# CLK_SYNC.net
KiCad netlist of a schematic drawn in Altium Designer
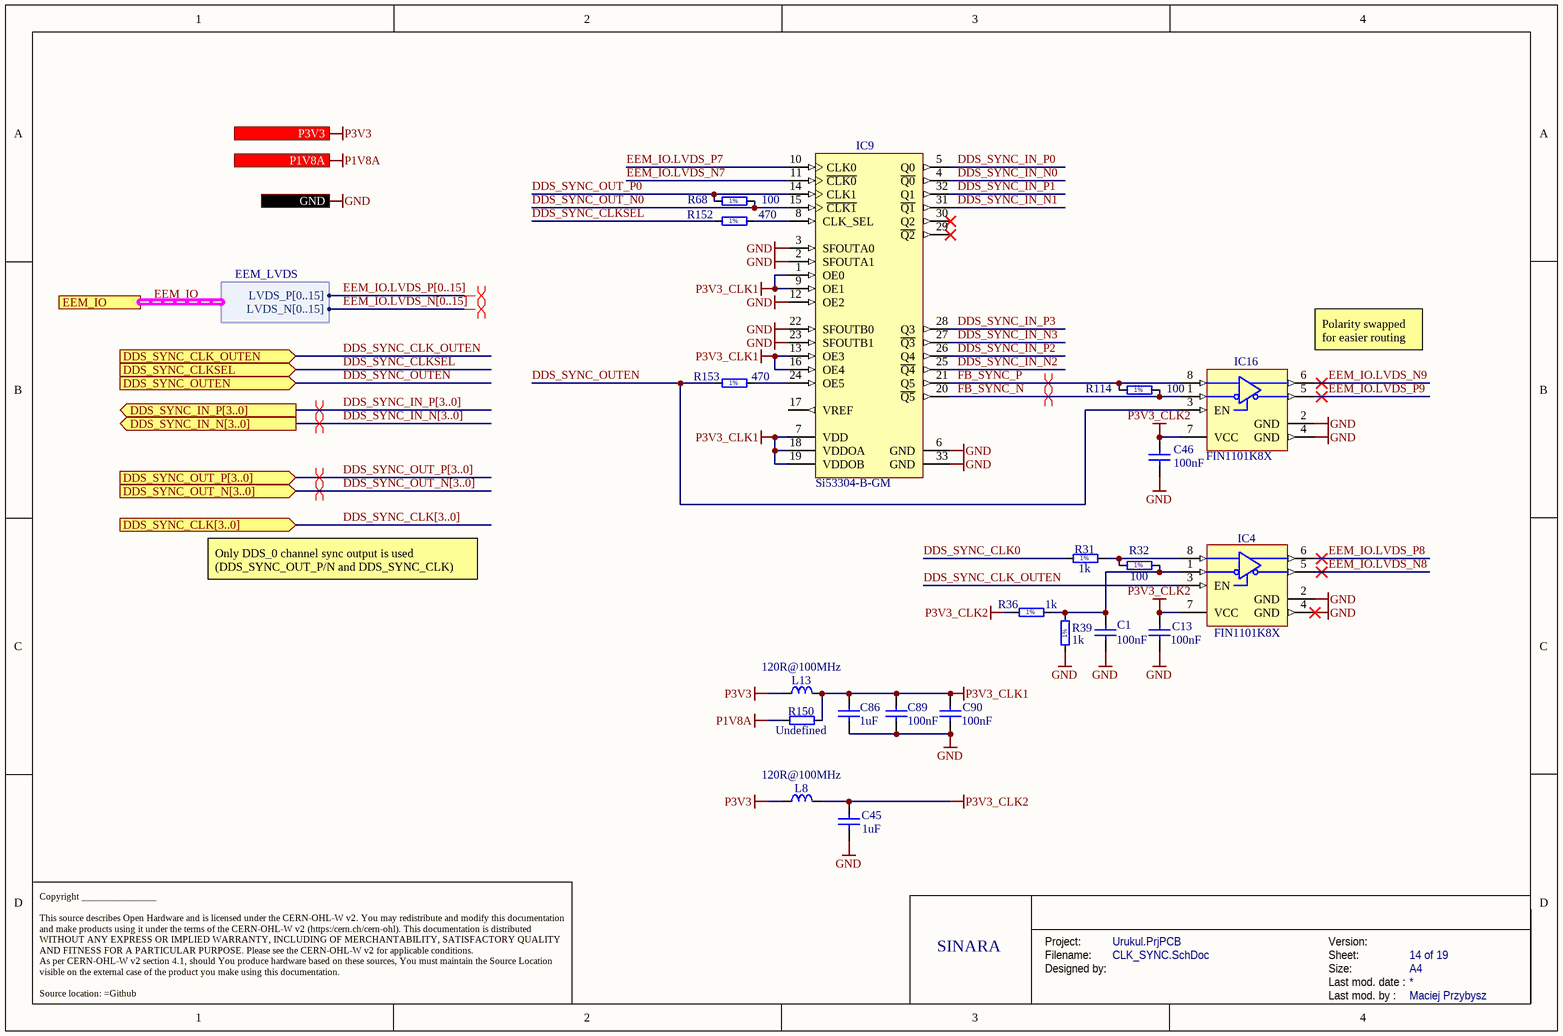
[diagram p0: CLK_SYNC.SchDoc]

(export (version "E")
  (design (tool "Eeschema 10.0.6"))
  (components
    (comp (ref "C1")
      (value "100nF")
      (footprint "CAPC1005X55N")
      (description "Non-polarised capacitor")
      (fields
        (field (name "PART NUMBER") "CC0402_100NF_16V_10%_X5R")
        (field (name "VOLTAGE") "16V")
        (field (name "AUTHOR") "CERN DEM JLC")
      )
      (libsource (lib "Capacitors") (part "Capacitor - non polarized"))
    )
    (comp (ref "C13")
      (value "100nF")
      (footprint "CAPC1005X55N")
      (description "Non-polarised capacitor")
      (fields
        (field (name "PART NUMBER") "CC0402_100NF_16V_10%_X5R")
        (field (name "VOLTAGE") "16V")
        (field (name "AUTHOR") "CERN DEM JLC")
      )
      (libsource (lib "Capacitors") (part "Capacitor - non polarized"))
    )
    (comp (ref "C45")
      (value "1uF")
      (footprint "CAPC1005X55N")
      (description "Non-polarised capacitor")
      (fields
        (field (name "PART NUMBER") "CC0402_1UF_16V_10%_X5R")
        (field (name "VOLTAGE") "16V")
        (field (name "AUTHOR") "CERN DEM JLC")
      )
      (libsource (lib "Capacitors") (part "Capacitor - non polarized"))
    )
    (comp (ref "C46")
      (value "100nF")
      (footprint "CAPC1005X55N")
      (description "Non-polarised capacitor")
      (fields
        (field (name "PART NUMBER") "CC0402_100NF_16V_10%_X5R")
        (field (name "VOLTAGE") "16V")
        (field (name "AUTHOR") "CERN DEM JLC")
      )
      (libsource (lib "Capacitors") (part "Capacitor - non polarized"))
    )
    (comp (ref "C86")
      (value "1uF")
      (footprint "CAPC1005X55N")
      (description "Non-polarised capacitor")
      (fields
        (field (name "PART NUMBER") "CC0402_1UF_16V_10%_X5R")
        (field (name "VOLTAGE") "16V")
        (field (name "AUTHOR") "CERN DEM JLC")
      )
      (libsource (lib "Capacitors") (part "Capacitor - non polarized"))
    )
    (comp (ref "C89")
      (value "100nF")
      (footprint "CAPC1005X55N")
      (description "Non-polarised capacitor")
      (fields
        (field (name "PART NUMBER") "CC0402_100NF_16V_10%_X5R")
        (field (name "VOLTAGE") "16V")
        (field (name "AUTHOR") "CERN DEM JLC")
      )
      (libsource (lib "Capacitors") (part "Capacitor - non polarized"))
    )
    (comp (ref "C90")
      (value "100nF")
      (footprint "CAPC1005X55N")
      (description "Non-polarised capacitor")
      (fields
        (field (name "PART NUMBER") "CC0402_100NF_16V_10%_X5R")
        (field (name "VOLTAGE") "16V")
        (field (name "AUTHOR") "CERN DEM JLC")
      )
      (libsource (lib "Capacitors") (part "Capacitor - non polarized"))
    )
    (comp (ref "IC4")
      (value "FIN1101K8X")
      (footprint "SOP50P310X90-8N")
      (description "LVDS Single Port High Speed Repeater")
      (fields (field (name "MANUFACTURER") "FAIRCHILD SEMICONDUCTOR") (field (name "AUTHOR") "CERN DEM JLC"))
      (libsource (lib "ICs And Semiconductors") (part "FIN1101K8X"))
    )
    (comp (ref "IC9")
      (value "Si53304-B-GM")
      (footprint "SLAB-QFN-32-2150x2150TP_M")
      (fields (field (name "MANUFACTURER") "Silicon Labs"))
      (libsource (lib "Altium Content Vault") (part "SLAB-Si533X4-QFN-32-33"))
    )
    (comp (ref "IC16")
      (value "FIN1101K8X")
      (footprint "SOP50P310X90-8N")
      (description "LVDS Single Port High Speed Repeater")
      (fields (field (name "MANUFACTURER") "FAIRCHILD SEMICONDUCTOR") (field (name "AUTHOR") "CERN DEM JLC"))
      (libsource (lib "ICs And Semiconductors") (part "FIN1101K8X"))
    )
    (comp (ref "L8")
      (value "120R@100MHz")
      (footprint "INDC1608X95N")
      (description "Inductor")
      (fields
        (field (name "PART NUMBER") "IND0603_MURATA_BLM18PG121SN1D")
        (field (name "POWER") "2A")
        (field (name "AUTHOR") "CERN DEM BC")
      )
      (libsource (lib "Inductors & Transformers") (part "Inductor"))
    )
    (comp (ref "L13")
      (value "120R@100MHz")
      (footprint "INDC1608X95N")
      (description "Inductor")
      (fields
        (field (name "PART NUMBER") "IND0603_MURATA_BLM18PG121SN1D")
        (field (name "POWER") "2A")
        (field (name "AUTHOR") "CERN DEM BC")
      )
      (libsource (lib "Inductors & Transformers") (part "Inductor"))
    )
    (comp (ref "R31")
      (value "1k")
      (footprint "RESC1005X40N")
      (description "Resistor - 1%")
      (fields
        (field (name "PART NUMBER") "R0402_1K_1%_0.0625W_100PPM")
        (field (name "POWER") "0.0625W")
        (field (name "AUTHOR") "CERN DEM JLC")
      )
      (libsource (lib "Resistors") (part "Resistor - 1%"))
    )
    (comp (ref "R32")
      (value "100")
      (footprint "RESC1005X40N")
      (description "Resistor - 1%")
      (fields
        (field (name "PART NUMBER") "R0402_100R_1%_0.0625W_100PPM")
        (field (name "POWER") "0.0625W")
        (field (name "AUTHOR") "CERN DEM JLC")
      )
      (libsource (lib "Resistors") (part "Resistor - 1%"))
    )
    (comp (ref "R36")
      (value "1k")
      (footprint "RESC1005X40N")
      (description "Resistor - 1%")
      (fields
        (field (name "PART NUMBER") "R0402_1K_1%_0.0625W_100PPM")
        (field (name "POWER") "0.0625W")
        (field (name "AUTHOR") "CERN DEM JLC")
      )
      (libsource (lib "Resistors") (part "Resistor - 1%"))
    )
    (comp (ref "R39")
      (value "1k")
      (footprint "RESC1005X40N")
      (description "Resistor - 1%")
      (fields
        (field (name "PART NUMBER") "R0402_1K_1%_0.0625W_100PPM")
        (field (name "POWER") "0.0625W")
        (field (name "AUTHOR") "CERN DEM JLC")
      )
      (libsource (lib "Resistors") (part "Resistor - 1%"))
    )
    (comp (ref "R68")
      (value "100")
      (footprint "RESC1005X40N")
      (description "Resistor - 1%")
      (fields
        (field (name "PART NUMBER") "R0402_100R_1%_0.0625W_100PPM")
        (field (name "POWER") "0.0625W")
        (field (name "AUTHOR") "CERN DEM JLC")
      )
      (libsource (lib "Resistors") (part "Resistor - 1%"))
    )
    (comp (ref "R114")
      (value "100")
      (footprint "RESC1005X40N")
      (description "Resistor - 1%")
      (fields
        (field (name "PART NUMBER") "R0402_100R_1%_0.0625W_100PPM")
        (field (name "POWER") "0.0625W")
        (field (name "AUTHOR") "CERN DEM JLC")
      )
      (libsource (lib "Resistors") (part "Resistor - 1%"))
    )
    (comp (ref "R150")
      (value "Undefined")
      (footprint "RESC1608X55N")
      (description "Resistor")
      (fields (field (name "PART NUMBER") "R0603_NO-VALUE") (field (name "AUTHOR") "CERN DEM JLC"))
      (libsource (lib "Resistors") (part "Resistor"))
    )
    (comp (ref "R152")
      (value "470")
      (footprint "RESC1005X40N")
      (description "Resistor - 1%")
      (fields
        (field (name "PART NUMBER") "R0402_470R_1%_0.0625W_100PPM")
        (field (name "POWER") "0.0625W")
        (field (name "AUTHOR") "CERN DEM JLC")
      )
      (libsource (lib "Resistors") (part "Resistor - 1%"))
    )
    (comp (ref "R153")
      (value "470")
      (footprint "RESC1005X40N")
      (description "Resistor - 1%")
      (fields
        (field (name "PART NUMBER") "R0402_470R_1%_0.0625W_100PPM")
        (field (name "POWER") "0.0625W")
        (field (name "AUTHOR") "CERN DEM JLC")
      )
      (libsource (lib "Resistors") (part "Resistor - 1%"))
    )
  )
  (nets
    (net (code "37") (name "/DDS_SYNC_CLK0") (class "Default")
      (node (ref "R31") (pin "1") (pinfunction "1_1") (pintype "passive"))
    )
    (net (code "38") (name "/DDS_SYNC_CLKSEL") (class "Default")
      (node (ref "R152") (pin "1") (pinfunction "1_1") (pintype "passive"))
    )
    (net (code "40") (name "/DDS_SYNC_CLK_OUTEN") (class "Default")
      (node (ref "IC4") (pin "3") (pinfunction "EN_3") (pintype "input"))
    )
    (net (code "41") (name "/DDS_SYNC_IN_N0") (class "Default")
      (node (ref "IC9") (pin "4") (pinfunction "~{Q0}_4") (pintype "output"))
    )
    (net (code "42") (name "/DDS_SYNC_IN_N1") (class "Default")
      (node (ref "IC9") (pin "31") (pinfunction "~{Q1}_31") (pintype "output"))
    )
    (net (code "43") (name "/DDS_SYNC_IN_N2") (class "Default")
      (node (ref "IC9") (pin "25") (pinfunction "~{Q4}_25") (pintype "output"))
    )
    (net (code "44") (name "/DDS_SYNC_IN_N3") (class "Default")
      (node (ref "IC9") (pin "27") (pinfunction "~{Q3}_27") (pintype "output"))
    )
    (net (code "46") (name "/DDS_SYNC_IN_P0") (class "Default")
      (node (ref "IC9") (pin "5") (pinfunction "Q0_5") (pintype "output"))
    )
    (net (code "47") (name "/DDS_SYNC_IN_P1") (class "Default")
      (node (ref "IC9") (pin "32") (pinfunction "Q1_32") (pintype "output"))
    )
    (net (code "48") (name "/DDS_SYNC_IN_P2") (class "Default")
      (node (ref "IC9") (pin "26") (pinfunction "Q4_26") (pintype "output"))
    )
    (net (code "49") (name "/DDS_SYNC_IN_P3") (class "Default")
      (node (ref "IC9") (pin "28") (pinfunction "Q3_28") (pintype "output"))
    )
    (net (code "51") (name "/DDS_SYNC_OUTEN") (class "Default")
      (node (ref "IC16") (pin "3") (pinfunction "EN_3") (pintype "input"))
      (node (ref "R153") (pin "1") (pinfunction "1_1") (pintype "passive"))
    )
    (net (code "52") (name "/DDS_SYNC_OUT_N0") (class "Default")
      (node (ref "IC9") (pin "15") (pinfunction "~{CLK1}_15") (pintype "input"))
      (node (ref "R68") (pin "2") (pinfunction "2_2") (pintype "passive"))
    )
    (net (code "54") (name "/DDS_SYNC_OUT_P0") (class "Default")
      (node (ref "IC9") (pin "14") (pinfunction "CLK1_14") (pintype "input"))
      (node (ref "R68") (pin "1") (pinfunction "1_1") (pintype "passive"))
    )
    (net (code "56") (name "/EEM_IO.LVDS_N7") (class "Default")
      (node (ref "IC9") (pin "11") (pinfunction "~{CLK0}_11") (pintype "input"))
    )
    (net (code "57") (name "/EEM_IO.LVDS_N8") (class "Default")
      (node (ref "IC4") (pin "5") (pinfunction "DOUT-_5") (pintype "output"))
    )
    (net (code "58") (name "/EEM_IO.LVDS_N9") (class "Default")
      (node (ref "IC16") (pin "6") (pinfunction "DOUT+_6") (pintype "output"))
    )
    (net (code "60") (name "/EEM_IO.LVDS_P7") (class "Default")
      (node (ref "IC9") (pin "10") (pinfunction "CLK0_10") (pintype "input"))
    )
    (net (code "61") (name "/EEM_IO.LVDS_P8") (class "Default")
      (node (ref "IC4") (pin "6") (pinfunction "DOUT+_6") (pintype "output"))
    )
    (net (code "62") (name "/EEM_IO.LVDS_P9") (class "Default")
      (node (ref "IC16") (pin "5") (pinfunction "DOUT-_5") (pintype "output"))
    )
    (net (code "65") (name "/FB_SYNC_N") (class "Default")
      (node (ref "IC16") (pin "1") (pinfunction "RIN-_1") (pintype "input"))
      (node (ref "IC9") (pin "20") (pinfunction "~{Q5}_20") (pintype "output"))
      (node (ref "R114") (pin "2") (pinfunction "2_2") (pintype "passive"))
    )
    (net (code "66") (name "/FB_SYNC_P") (class "Default")
      (node (ref "IC16") (pin "8") (pinfunction "RIN+_8") (pintype "input"))
      (node (ref "IC9") (pin "21") (pinfunction "Q5_21") (pintype "output"))
      (node (ref "R114") (pin "1") (pinfunction "1_1") (pintype "passive"))
    )
    (net (code "67") (name "GND") (class "Default")
      (node (ref "C1") (pin "1") (pinfunction "1_1") (pintype "passive"))
      (node (ref "C13") (pin "1") (pinfunction "1_1") (pintype "passive"))
      (node (ref "C45") (pin "1") (pinfunction "1_1") (pintype "passive"))
      (node (ref "C46") (pin "1") (pinfunction "1_1") (pintype "passive"))
      (node (ref "C86") (pin "1") (pinfunction "1_1") (pintype "passive"))
      (node (ref "C89") (pin "1") (pinfunction "1_1") (pintype "passive"))
      (node (ref "C90") (pin "1") (pinfunction "1_1") (pintype "passive"))
      (node (ref "IC16") (pin "2") (pinfunction "GND_2") (pintype "power_in"))
      (node (ref "IC16") (pin "4") (pinfunction "GND_4") (pintype "output"))
      (node (ref "IC4") (pin "2") (pinfunction "GND_2") (pintype "power_in"))
      (node (ref "IC4") (pin "4") (pinfunction "GND_4") (pintype "output"))
      (node (ref "IC9") (pin "12") (pinfunction "OE2_12") (pintype "input"))
      (node (ref "IC9") (pin "2") (pinfunction "SFOUTA1_2") (pintype "input"))
      (node (ref "IC9") (pin "22") (pinfunction "SFOUTB0_22") (pintype "input"))
      (node (ref "IC9") (pin "23") (pinfunction "SFOUTB1_23") (pintype "input"))
      (node (ref "IC9") (pin "3") (pinfunction "SFOUTA0_3") (pintype "input"))
      (node (ref "IC9") (pin "33") (pinfunction "GND_33") (pintype "power_in"))
      (node (ref "IC9") (pin "6") (pinfunction "GND_6") (pintype "power_in"))
      (node (ref "R39") (pin "1") (pinfunction "1_1") (pintype "passive"))
    )
    (net (code "68") (name "Net-(IC4-RIN+)") (class "Default")
      (node (ref "IC4") (pin "8") (pinfunction "RIN+_8") (pintype "input"))
      (node (ref "R31") (pin "2") (pinfunction "2_2") (pintype "passive"))
      (node (ref "R32") (pin "1") (pinfunction "1_1") (pintype "passive"))
    )
    (net (code "69") (name "Net-(IC4-RIN-)") (class "Default")
      (node (ref "C1") (pin "2") (pinfunction "2_2") (pintype "passive"))
      (node (ref "IC4") (pin "1") (pinfunction "RIN-_1") (pintype "input"))
      (node (ref "R32") (pin "2") (pinfunction "2_2") (pintype "passive"))
      (node (ref "R36") (pin "2") (pinfunction "2_2") (pintype "passive"))
      (node (ref "R39") (pin "2") (pinfunction "2_2") (pintype "passive"))
    )
    (net (code "70") (name "Net-(IC9-CLK_SEL)") (class "Default")
      (node (ref "IC9") (pin "8") (pinfunction "CLK_SEL_8") (pintype "input"))
      (node (ref "R152") (pin "2") (pinfunction "2_2") (pintype "passive"))
    )
    (net (code "71") (name "Net-(IC9-OE5)") (class "Default")
      (node (ref "IC9") (pin "24") (pinfunction "OE5_24") (pintype "input"))
      (node (ref "R153") (pin "2") (pinfunction "2_2") (pintype "passive"))
    )
    (net (code "72") (name "P1V8A") (class "Default")
      (node (ref "R150") (pin "1") (pinfunction "1_1") (pintype "passive"))
    )
    (net (code "73") (name "P3V3") (class "Default")
      (node (ref "L13") (pin "2") (pinfunction "2_2") (pintype "passive"))
      (node (ref "L8") (pin "2") (pinfunction "2_2") (pintype "passive"))
    )
    (net (code "74") (name "P3V3_CLK1") (class "Default")
      (node (ref "C86") (pin "2") (pinfunction "2_2") (pintype "passive"))
      (node (ref "C89") (pin "2") (pinfunction "2_2") (pintype "passive"))
      (node (ref "C90") (pin "2") (pinfunction "2_2") (pintype "passive"))
      (node (ref "IC9") (pin "1") (pinfunction "OE0_1") (pintype "input"))
      (node (ref "IC9") (pin "13") (pinfunction "OE3_13") (pintype "input"))
      (node (ref "IC9") (pin "16") (pinfunction "OE4_16") (pintype "input"))
      (node (ref "IC9") (pin "18") (pinfunction "VDDOA_18") (pintype "power_in"))
      (node (ref "IC9") (pin "19") (pinfunction "VDDOB_19") (pintype "power_in"))
      (node (ref "IC9") (pin "7") (pinfunction "VDD_7") (pintype "power_in"))
      (node (ref "IC9") (pin "9") (pinfunction "OE1_9") (pintype "input"))
      (node (ref "L13") (pin "1") (pinfunction "1_1") (pintype "passive"))
      (node (ref "R150") (pin "2") (pinfunction "2_2") (pintype "passive"))
    )
    (net (code "75") (name "P3V3_CLK2") (class "Default")
      (node (ref "C13") (pin "2") (pinfunction "2_2") (pintype "passive"))
      (node (ref "C45") (pin "2") (pinfunction "2_2") (pintype "passive"))
      (node (ref "C46") (pin "2") (pinfunction "2_2") (pintype "passive"))
      (node (ref "IC16") (pin "7") (pinfunction "VCC_7") (pintype "power_in"))
      (node (ref "IC4") (pin "7") (pinfunction "VCC_7") (pintype "power_in"))
      (node (ref "L8") (pin "1") (pinfunction "1_1") (pintype "passive"))
      (node (ref "R36") (pin "1") (pinfunction "1_1") (pintype "passive"))
    )
    (net (code "76") (name "unconnected-(IC9-Q2-Pad30)") (class "Default")
      (node (ref "IC9") (pin "30") (pinfunction "Q2_30") (pintype "output+no_connect"))
    )
    (net (code "77") (name "unconnected-(IC9-VREF-Pad17)") (class "Default")
      (node (ref "IC9") (pin "17") (pinfunction "VREF_17") (pintype "output"))
    )
    (net (code "78") (name "unconnected-(IC9-~{Q2}-Pad29)") (class "Default")
      (node (ref "IC9") (pin "29") (pinfunction "~{Q2}_29") (pintype "output+no_connect"))
    )
  )
)
